# CAN_Bus_v2.net
KiCad netlist of a schematic drawn in Altium Designer
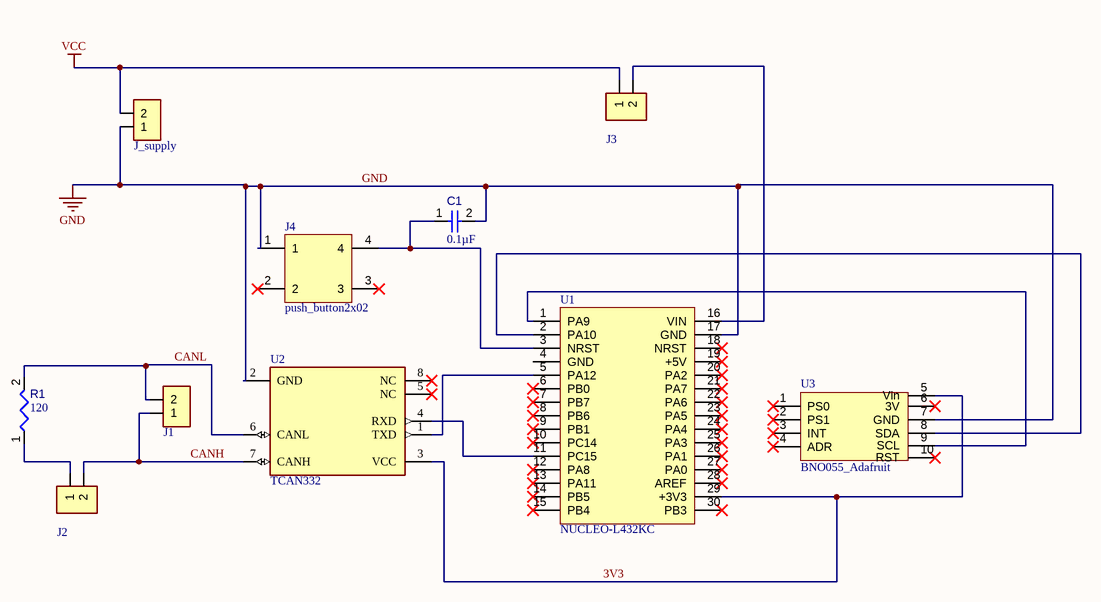
[diagram p0: CAN_Bus_v2.SchDoc]

(export (version "E")
  (design (tool "Eeschema 10.0.6"))
  (components
    (comp (ref "C1")
      (value "0.1µF")
      (footprint "KEMT-C315-THT-2")
      (fields (field (name "Comment") "ceramic_capacitor_throughhole"))
      (libsource (lib "Isae-Supaero") (part "CAP-NP-2"))
    )
    (comp (ref "J1")
      (value "Goldpin_1x02")
      (footprint "HDRV2W63P254_1x02")
      (libsource (lib "_Conn_PinHeaders") (part "Goldpin_1x02"))
    )
    (comp (ref "J2")
      (value "Goldpin_1x02")
      (footprint "HDRV2W63P254_1x02")
      (libsource (lib "") (part "Goldpin_1x02_1"))
    )
    (comp (ref "J3")
      (value "Goldpin_1x02")
      (footprint "HDRV2W63P254_1x02")
      (libsource (lib "") (part "Goldpin_1x02_1"))
    )
    (comp (ref "J4")
      (value "push_button2x02")
      (footprint "push_button2x02")
      (libsource (lib "_Conn_PinHeaders") (part "push_button2x02"))
    )
    (comp (ref "J_supply")
      (value "Goldpin_1x02")
      (footprint "HDRV2W63P254_1x02")
      (libsource (lib "_Conn_PinHeaders") (part "Goldpin_1x02"))
    )
    (comp (ref "R1")
      (value "120")
      (footprint "RESA60-630X240")
      (description "Axial Resistor, 2.21 KOhm, +/- 1%, 0.25 W, -55 to 155 degC, 2-Pin THD, RoHS, Bulk")
      (fields (field (name "TOLERANCE") "1%") (field (name "POWER") "250mW"))
      (libsource (lib "Isae-Supaero") (part "RES-2"))
    )
    (comp (ref "U1")
      (value "NUCLEO-L432KC")
      (footprint "NUCLEO-L432KC")
      (description "Arm® Cortex®-M4 32-bit MCU, 24 MHz, 256 KB Flash")
      (fields (field (name "PN") "NUCLEO-L432KC"))
      (libsource (lib "_IC_MCU") (part "NUCLEO-L432KC"))
    )
    (comp (ref "U2")
      (value "TCAN332")
      (footprint "FP-DCN0008A-IPC_A")
      (description "Interface Circuit, PDSO8, CAN Transceiver")
      (libsource (lib "Isae-Supaero") (part "e2d0f06fcd32c080737956741cb589f"))
    )
    (comp (ref "U3")
      (value "BNO055_Adafruit")
      (footprint "BNO055_Adafruit")
      (description "Adafruit BNO055 9-dof IMU sensor")
      (libsource (lib "_IC_Measurement") (part "BNO055_Adafruit"))
    )
  )
  (nets
    (net (code "1") (name "/3V3") (class "Default")
      (node (ref "U1") (pin "29") (pinfunction "+3V3_29") (pintype "power_in"))
      (node (ref "U2") (pin "3") (pinfunction "VCC_3") (pintype "power_in"))
      (node (ref "U3") (pin "5") (pinfunction "Vin_5") (pintype "passive"))
    )
    (net (code "2") (name "/CANH") (class "Default")
      (node (ref "J1") (pin "1") (pinfunction "1_1") (pintype "passive"))
      (node (ref "J2") (pin "2") (pinfunction "2_2") (pintype "passive"))
      (node (ref "U2") (pin "7") (pinfunction "CANH_7") (pintype "bidirectional"))
    )
    (net (code "3") (name "/CANL") (class "Default")
      (node (ref "J1") (pin "2") (pinfunction "2_2") (pintype "passive"))
      (node (ref "R1") (pin "2") (pinfunction "2_2") (pintype "passive"))
      (node (ref "U2") (pin "6") (pinfunction "CANL_6") (pintype "bidirectional"))
    )
    (net (code "4") (name "GND") (class "Default")
      (node (ref "C1") (pin "2") (pinfunction "2_2") (pintype "passive"))
      (node (ref "J4") (pin "1") (pinfunction "1_1") (pintype "passive"))
      (node (ref "J_supply") (pin "1") (pinfunction "1_1") (pintype "passive"))
      (node (ref "U1") (pin "17") (pinfunction "GND_17") (pintype "power_in"))
      (node (ref "U2") (pin "2") (pinfunction "GND_2") (pintype "power_in"))
      (node (ref "U3") (pin "7") (pinfunction "GND_7") (pintype "passive"))
    )
    (net (code "5") (name "Net-(C1-Pad1)") (class "Default")
      (node (ref "C1") (pin "1") (pinfunction "1_1") (pintype "passive"))
      (node (ref "J4") (pin "4") (pinfunction "4_4") (pintype "passive"))
      (node (ref "U1") (pin "3") (pinfunction "NRST_3") (pintype "passive"))
    )
    (net (code "6") (name "Net-(J2-Pad1)") (class "Default")
      (node (ref "J2") (pin "1") (pinfunction "1_1") (pintype "passive"))
      (node (ref "R1") (pin "1") (pinfunction "1_1") (pintype "passive"))
    )
    (net (code "7") (name "Net-(U1-PA9)") (class "Default")
      (node (ref "U1") (pin "1") (pinfunction "PA9_1") (pintype "passive"))
      (node (ref "U3") (pin "9") (pinfunction "SCL_9") (pintype "passive"))
    )
    (net (code "8") (name "Net-(U1-PA10)") (class "Default")
      (node (ref "U1") (pin "2") (pinfunction "PA10_2") (pintype "passive"))
      (node (ref "U3") (pin "8") (pinfunction "SDA_8") (pintype "passive"))
    )
    (net (code "9") (name "Net-(U1-PA12)") (class "Default")
      (node (ref "U1") (pin "5") (pinfunction "PA12_5") (pintype "passive"))
      (node (ref "U2") (pin "1") (pinfunction "TXD_1") (pintype "output"))
    )
    (net (code "10") (name "Net-(U1-PC15)") (class "Default")
      (node (ref "U1") (pin "11") (pinfunction "PC15_11") (pintype "passive"))
      (node (ref "U2") (pin "4") (pinfunction "RXD_4") (pintype "output"))
    )
    (net (code "11") (name "Net-(U1-VIN)") (class "Default")
      (node (ref "J3") (pin "2") (pinfunction "2_2") (pintype "passive"))
      (node (ref "U1") (pin "16") (pinfunction "VIN_16") (pintype "power_in"))
    )
    (net (code "12") (name "VCC") (class "Default")
      (node (ref "J3") (pin "1") (pinfunction "1_1") (pintype "passive"))
      (node (ref "J_supply") (pin "2") (pinfunction "2_2") (pintype "passive"))
    )
    (net (code "13") (name "unconnected-(J4-Pad2)") (class "Default")
      (node (ref "J4") (pin "2") (pinfunction "2_2") (pintype "passive+no_connect"))
    )
    (net (code "14") (name "unconnected-(J4-Pad3)") (class "Default")
      (node (ref "J4") (pin "3") (pinfunction "3_3") (pintype "passive+no_connect"))
    )
    (net (code "15") (name "unconnected-(U1-+5V-Pad19)") (class "Default")
      (node (ref "U1") (pin "19") (pinfunction "+5V_19") (pintype "power_in+no_connect"))
    )
    (net (code "16") (name "unconnected-(U1-AREF-Pad28)") (class "Default")
      (node (ref "U1") (pin "28") (pinfunction "AREF_28") (pintype "power_in+no_connect"))
    )
    (net (code "17") (name "unconnected-(U1-GND-Pad4)") (class "Default")
      (node (ref "U1") (pin "4") (pinfunction "GND_4") (pintype "power_in"))
    )
    (net (code "18") (name "unconnected-(U1-NRST-Pad18)") (class "Default")
      (node (ref "U1") (pin "18") (pinfunction "NRST_18") (pintype "passive+no_connect"))
    )
    (net (code "19") (name "unconnected-(U1-PA0-Pad27)") (class "Default")
      (node (ref "U1") (pin "27") (pinfunction "PA0_27") (pintype "passive+no_connect"))
    )
    (net (code "20") (name "unconnected-(U1-PA1-Pad26)") (class "Default")
      (node (ref "U1") (pin "26") (pinfunction "PA1_26") (pintype "passive+no_connect"))
    )
    (net (code "21") (name "unconnected-(U1-PA2-Pad20)") (class "Default")
      (node (ref "U1") (pin "20") (pinfunction "PA2_20") (pintype "passive+no_connect"))
    )
    (net (code "22") (name "unconnected-(U1-PA3-Pad25)") (class "Default")
      (node (ref "U1") (pin "25") (pinfunction "PA3_25") (pintype "passive+no_connect"))
    )
    (net (code "23") (name "unconnected-(U1-PA4-Pad24)") (class "Default")
      (node (ref "U1") (pin "24") (pinfunction "PA4_24") (pintype "passive+no_connect"))
    )
    (net (code "24") (name "unconnected-(U1-PA5-Pad23)") (class "Default")
      (node (ref "U1") (pin "23") (pinfunction "PA5_23") (pintype "passive+no_connect"))
    )
    (net (code "25") (name "unconnected-(U1-PA6-Pad22)") (class "Default")
      (node (ref "U1") (pin "22") (pinfunction "PA6_22") (pintype "passive+no_connect"))
    )
    (net (code "26") (name "unconnected-(U1-PA7-Pad21)") (class "Default")
      (node (ref "U1") (pin "21") (pinfunction "PA7_21") (pintype "passive+no_connect"))
    )
    (net (code "27") (name "unconnected-(U1-PA8-Pad12)") (class "Default")
      (node (ref "U1") (pin "12") (pinfunction "PA8_12") (pintype "passive+no_connect"))
    )
    (net (code "28") (name "unconnected-(U1-PA11-Pad13)") (class "Default")
      (node (ref "U1") (pin "13") (pinfunction "PA11_13") (pintype "passive+no_connect"))
    )
    (net (code "29") (name "unconnected-(U1-PB0-Pad6)") (class "Default")
      (node (ref "U1") (pin "6") (pinfunction "PB0_6") (pintype "passive+no_connect"))
    )
    (net (code "30") (name "unconnected-(U1-PB1-Pad9)") (class "Default")
      (node (ref "U1") (pin "9") (pinfunction "PB1_9") (pintype "passive+no_connect"))
    )
    (net (code "31") (name "unconnected-(U1-PB3-Pad30)") (class "Default")
      (node (ref "U1") (pin "30") (pinfunction "PB3_30") (pintype "passive+no_connect"))
    )
    (net (code "32") (name "unconnected-(U1-PB4-Pad15)") (class "Default")
      (node (ref "U1") (pin "15") (pinfunction "PB4_15") (pintype "passive+no_connect"))
    )
    (net (code "33") (name "unconnected-(U1-PB5-Pad14)") (class "Default")
      (node (ref "U1") (pin "14") (pinfunction "PB5_14") (pintype "passive+no_connect"))
    )
    (net (code "34") (name "unconnected-(U1-PB6-Pad8)") (class "Default")
      (node (ref "U1") (pin "8") (pinfunction "PB6_8") (pintype "passive+no_connect"))
    )
    (net (code "35") (name "unconnected-(U1-PB7-Pad7)") (class "Default")
      (node (ref "U1") (pin "7") (pinfunction "PB7_7") (pintype "passive+no_connect"))
    )
    (net (code "36") (name "unconnected-(U1-PC14-Pad10)") (class "Default")
      (node (ref "U1") (pin "10") (pinfunction "PC14_10") (pintype "passive+no_connect"))
    )
    (net (code "37") (name "unconnected-(U2-NC-Pad5)") (class "Default")
      (node (ref "U2") (pin "5") (pinfunction "NC_5") (pintype "passive+no_connect"))
    )
    (net (code "38") (name "unconnected-(U2-NC-Pad8)") (class "Default")
      (node (ref "U2") (pin "8") (pinfunction "NC_8") (pintype "passive+no_connect"))
    )
    (net (code "39") (name "unconnected-(U3-3V-Pad6)") (class "Default")
      (node (ref "U3") (pin "6") (pinfunction "3V_6") (pintype "passive+no_connect"))
    )
    (net (code "40") (name "unconnected-(U3-ADR-Pad4)") (class "Default")
      (node (ref "U3") (pin "4") (pinfunction "ADR_4") (pintype "passive+no_connect"))
    )
    (net (code "41") (name "unconnected-(U3-INT-Pad3)") (class "Default")
      (node (ref "U3") (pin "3") (pinfunction "INT_3") (pintype "passive+no_connect"))
    )
    (net (code "42") (name "unconnected-(U3-PS0-Pad1)") (class "Default")
      (node (ref "U3") (pin "1") (pinfunction "PS0_1") (pintype "passive+no_connect"))
    )
    (net (code "43") (name "unconnected-(U3-PS1-Pad2)") (class "Default")
      (node (ref "U3") (pin "2") (pinfunction "PS1_2") (pintype "passive+no_connect"))
    )
    (net (code "44") (name "unconnected-(U3-RST-Pad10)") (class "Default")
      (node (ref "U3") (pin "10") (pinfunction "RST_10") (pintype "passive+no_connect"))
    )
  )
)
